# Dashboard.net
KiCad netlist of a schematic drawn in Altium Designer
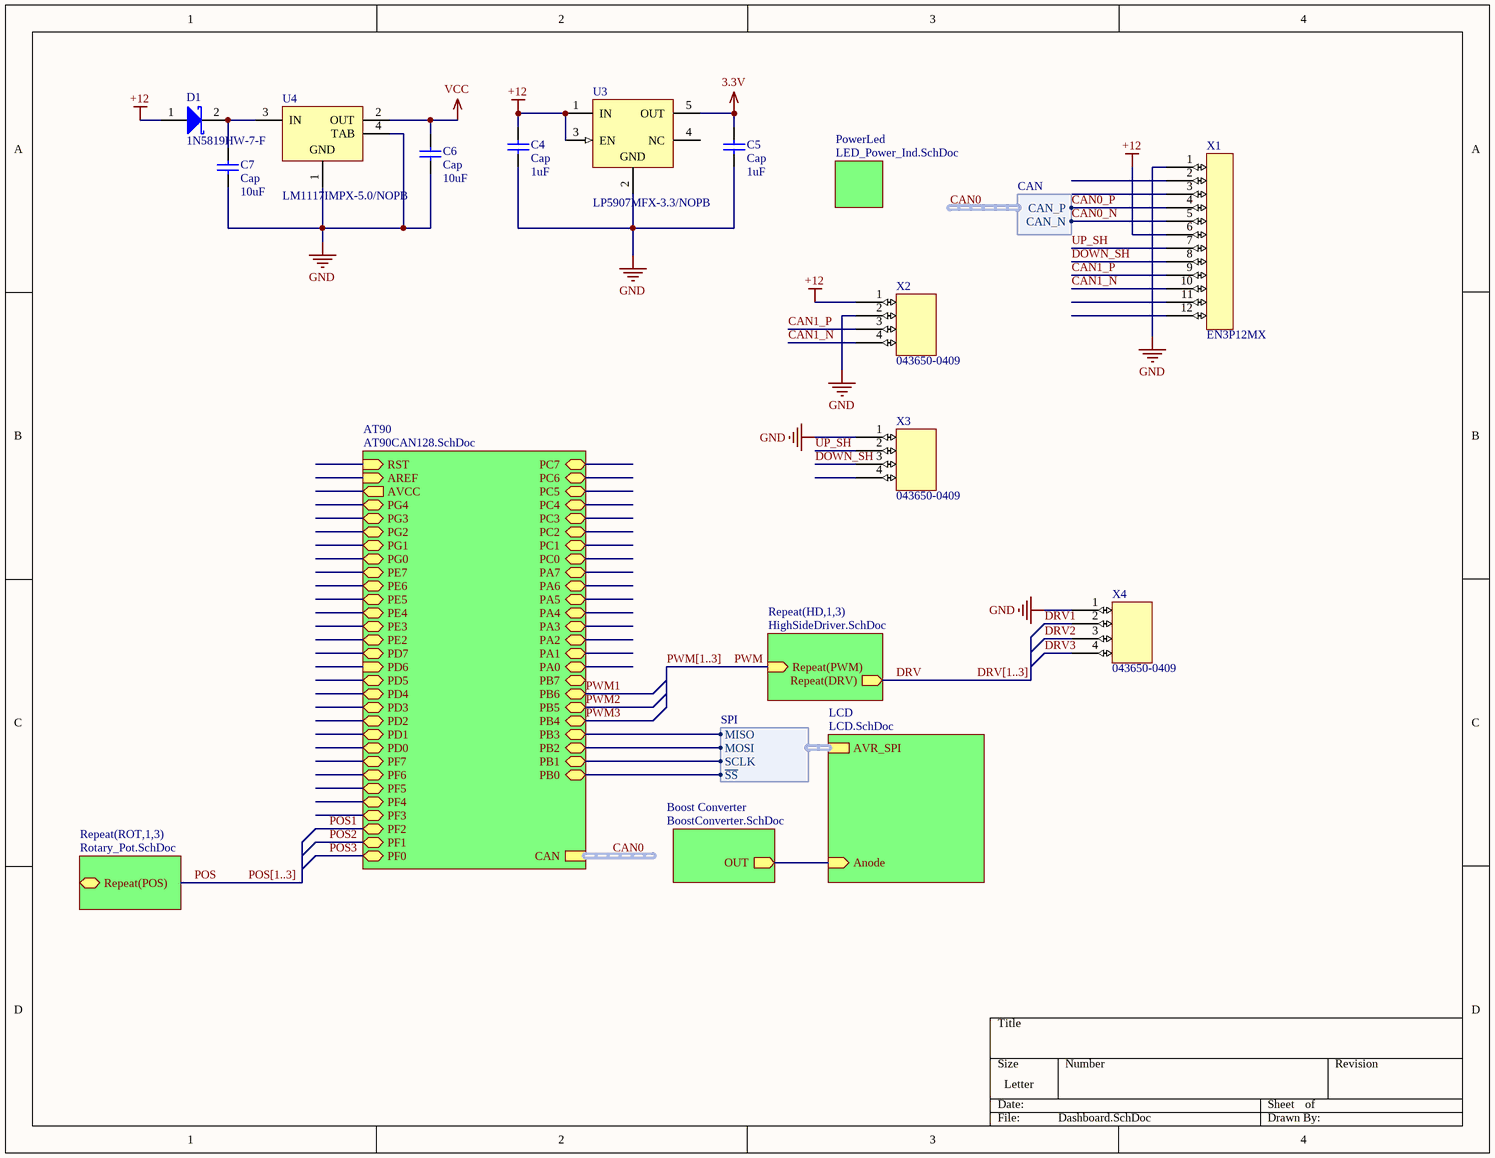
[diagram p0: Dashboard.SchDoc]

(export (version "E")
  (design (tool "Eeschema 10.0.6"))
  (components
    (comp (ref "C4")
      (value "Cap")
      (footprint "1608[0603]")
      (description "Capacitor")
      (fields (field (name "ALTIUM_VALUE") "1uF") (field (name "PUBLISHER") "Altium Limited"))
      (libsource (lib "Miscellaneous Devices") (part "Cap"))
    )
    (comp (ref "C5")
      (value "Cap")
      (footprint "1608[0603]")
      (description "Capacitor")
      (fields (field (name "ALTIUM_VALUE") "1uF") (field (name "PUBLISHER") "Altium Limited"))
      (libsource (lib "Miscellaneous Devices") (part "Cap"))
    )
    (comp (ref "C6")
      (value "Cap")
      (footprint "1608[0603]")
      (description "Capacitor")
      (fields (field (name "ALTIUM_VALUE") "10uF") (field (name "PUBLISHER") "Altium Limited"))
      (libsource (lib "Miscellaneous Devices") (part "Cap"))
    )
    (comp (ref "C7")
      (value "Cap")
      (footprint "1608[0603]")
      (description "Capacitor")
      (fields (field (name "ALTIUM_VALUE") "10uF") (field (name "PUBLISHER") "Altium Limited"))
      (libsource (lib "Miscellaneous Devices") (part "Cap"))
    )
    (comp (ref "D1")
      (value "1N5819HW-7-F")
      (footprint "DIOD-SOD-123-2_V")
      (fields (field (name "MANUFACTURER") "Diodes Inc"))
      (libsource (lib "Altium Content Vault") (part "DIOD-DSKY-A1K2-2"))
    )
    (comp (ref "U3")
      (value "LP5907MFX-3.3/NOPB")
      (footprint "DBV0005A_L")
      (fields (field (name "MANUFACTURER") "Texas Instruments"))
      (libsource (lib "Altium Content Vault") (part "TI-LP5907-SOT-23-5"))
    )
    (comp (ref "U4")
      (value "LM1117IMPX-5.0/NOPB")
      (footprint "MP04A_M")
      (description "800mA Low-Dropout Linear Regulator, 4-pin SOT-223, Pb-Free")
      (fields (field (name "MANUFACTURER") "National Semiconductor"))
      (libsource (lib "Altium Content Vault") (part "PM-REG-LM1086-SOT4"))
    )
    (comp (ref "X1")
      (value "EN3P12MX")
      (footprint "EN3P12MX")
      (libsource (lib "IntLibrary") (part "EN3P12MX"))
    )
    (comp (ref "X2")
      (value "043650-0409")
      (footprint "043650-0409")
      (libsource (lib "") (part "043650-0409_1"))
    )
    (comp (ref "X3")
      (value "043650-0409")
      (footprint "043650-0409")
      (libsource (lib "") (part "043650-0409_1"))
    )
    (comp (ref "X4")
      (value "043650-0409")
      (footprint "043650-0409")
      (libsource (lib "IntLibrary") (part "043650-0409"))
    )
  )
  (nets
    (net (code "4") (name "+12") (class "Default")
      (node (ref "C4") (pin "1") (pinfunction "1_1") (pintype "passive"))
      (node (ref "D1") (pin "1") (pinfunction "A_1") (pintype "passive"))
      (node (ref "U3") (pin "1") (pinfunction "IN_1") (pintype "power_in"))
      (node (ref "U3") (pin "3") (pinfunction "EN_3") (pintype "input"))
      (node (ref "X1") (pin "6") (pintype "bidirectional"))
      (node (ref "X2") (pin "1") (pintype "bidirectional"))
    )
    (net (code "7") (name "/CAN0_N") (class "Default") (node (ref "X1") (pin "5") (pintype "bidirectional")))
    (net (code "8") (name "/CAN0_P") (class "Default") (node (ref "X1") (pin "4") (pintype "bidirectional")))
    (net (code "10") (name "/CAN1_N") (class "Default")
      (node (ref "X1") (pin "10") (pintype "bidirectional"))
      (node (ref "X2") (pin "4") (pintype "bidirectional"))
    )
    (net (code "11") (name "/CAN1_P") (class "Default")
      (node (ref "X1") (pin "9") (pintype "bidirectional"))
      (node (ref "X2") (pin "3") (pintype "bidirectional"))
    )
    (net (code "12") (name "/DOWN_SH") (class "Default")
      (node (ref "X1") (pin "8") (pintype "bidirectional"))
      (node (ref "X3") (pin "3") (pintype "bidirectional"))
    )
    (net (code "14") (name "/DRV1") (class "Default") (node (ref "X4") (pin "2") (pintype "bidirectional")))
    (net (code "15") (name "/DRV2") (class "Default") (node (ref "X4") (pin "3") (pintype "bidirectional")))
    (net (code "16") (name "/DRV3") (class "Default") (node (ref "X4") (pin "4") (pintype "bidirectional")))
    (net (code "76") (name "/UP_SH") (class "Default")
      (node (ref "X1") (pin "7") (pintype "bidirectional"))
      (node (ref "X3") (pin "2") (pintype "bidirectional"))
    )
    (net (code "79") (name "3.3V") (class "Default")
      (node (ref "C5") (pin "1") (pinfunction "1_1") (pintype "passive"))
      (node (ref "U3") (pin "5") (pinfunction "OUT_5") (pintype "power_in"))
    )
    (net (code "80") (name "GND") (class "Default")
      (node (ref "C4") (pin "2") (pinfunction "2_2") (pintype "passive"))
      (node (ref "C5") (pin "2") (pinfunction "2_2") (pintype "passive"))
      (node (ref "C6") (pin "2") (pinfunction "2_2") (pintype "passive"))
      (node (ref "C7") (pin "2") (pinfunction "2_2") (pintype "passive"))
      (node (ref "U3") (pin "2") (pinfunction "GND_2") (pintype "power_in"))
      (node (ref "U4") (pin "1") (pinfunction "GND_1") (pintype "power_in"))
      (node (ref "U4") (pin "4") (pinfunction "TAB_4") (pintype "power_in"))
      (node (ref "X1") (pin "1") (pintype "bidirectional"))
      (node (ref "X2") (pin "2") (pintype "bidirectional"))
      (node (ref "X3") (pin "1") (pintype "bidirectional"))
      (node (ref "X4") (pin "1") (pintype "bidirectional"))
    )
    (net (code "81") (name "Net-(D1-K)") (class "Default")
      (node (ref "C7") (pin "1") (pinfunction "1_1") (pintype "passive"))
      (node (ref "D1") (pin "2") (pinfunction "K_2") (pintype "passive"))
      (node (ref "U4") (pin "3") (pinfunction "IN_3") (pintype "power_in"))
    )
    (net (code "82") (name "VCC") (class "Default")
      (node (ref "C6") (pin "1") (pinfunction "1_1") (pintype "passive"))
      (node (ref "U4") (pin "2") (pinfunction "OUT_2") (pintype "power_in"))
    )
    (net (code "83") (name "unconnected-(U3-NC-Pad4)") (class "Default")
      (node (ref "U3") (pin "4") (pinfunction "NC_4") (pintype "passive"))
    )
    (net (code "84") (name "unconnected-(X1-Pad2)") (class "Default")
      (node (ref "X1") (pin "2") (pintype "bidirectional"))
    )
    (net (code "85") (name "unconnected-(X1-Pad3)") (class "Default")
      (node (ref "X1") (pin "3") (pintype "bidirectional"))
    )
    (net (code "86") (name "unconnected-(X1-Pad11)") (class "Default")
      (node (ref "X1") (pin "11") (pintype "bidirectional"))
    )
    (net (code "87") (name "unconnected-(X1-Pad12)") (class "Default")
      (node (ref "X1") (pin "12") (pintype "bidirectional"))
    )
    (net (code "88") (name "unconnected-(X3-Pad4)") (class "Default")
      (node (ref "X3") (pin "4") (pintype "bidirectional"))
    )
  )
)
